# Schema_6.net
KiCad netlist of a schematic drawn in EAGLE
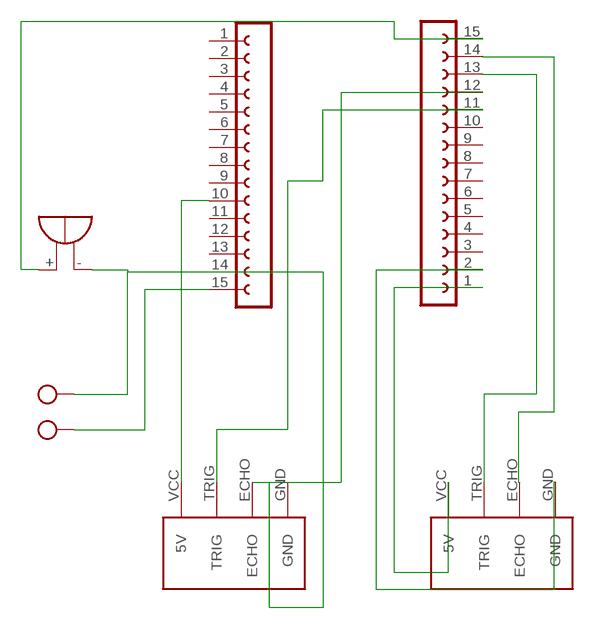
[diagram p0: schematic, sheet 1]

(export (version "E")
  (design (tool "Eeschema 10.0.6"))
  (components
    (comp (ref "J_ULTRASONIC_3")
      (value "HC-SR04")
      (footprint "eagle-import:HC-SR04_FOOTPRINT")
      (libsource (lib "eagle-import") (part "HC-SR04"))
    )
    (comp (ref "J_ULTRASONIC_4")
      (value "HC-SR04")
      (footprint "eagle-import:HC-SR04_FOOTPRINT")
      (libsource (lib "eagle-import") (part "HC-SR04"))
    )
    (comp (ref "SG2")
      (value "EB2505")
      (footprint "eagle-import:EB2505")
      (libsource (lib "eagle-import") (part "EB2505"))
    )
    (comp (ref "SV1")
      (value "FE15-1")
      (footprint "eagle-import:FE15")
      (libsource (lib "eagle-import") (part "FE15-1"))
    )
    (comp (ref "SV2")
      (value "FE15-1")
      (footprint "eagle-import:FE15")
      (libsource (lib "eagle-import") (part "FE15-1"))
    )
    (comp (ref "X1")
      (value "AK500/2-H")
      (footprint "eagle-import:AK500_2-H")
      (libsource (lib "eagle-import") (part "AK500/2-H"))
    )
  )
  (nets
    (net (code "1") (name "Net-(J_ULTRASONIC_3-5V)") (class "Default")
      (node (ref "J_ULTRASONIC_3") (pin "VCC") (pinfunction "5V_VCC") (pintype "bidirectional"))
      (node (ref "SV1") (pin "1") (pinfunction "1_1") (pintype "passive"))
    )
    (net (code "2") (name "Net-(J_ULTRASONIC_3-PadECHO)") (class "Default")
      (node (ref "J_ULTRASONIC_3") (pin "ECHO") (pinfunction "ECHO_ECHO") (pintype "bidirectional"))
      (node (ref "SV1") (pin "14") (pinfunction "14_14") (pintype "passive"))
    )
    (net (code "3") (name "Net-(J_ULTRASONIC_3-PadGND)") (class "Default")
      (node (ref "J_ULTRASONIC_3") (pin "GND") (pinfunction "GND_GND") (pintype "bidirectional"))
      (node (ref "SV1") (pin "2") (pinfunction "2_2") (pintype "passive"))
    )
    (net (code "4") (name "Net-(J_ULTRASONIC_3-PadTRIG)") (class "Default")
      (node (ref "J_ULTRASONIC_3") (pin "TRIG") (pinfunction "TRIG_TRIG") (pintype "bidirectional"))
      (node (ref "SV1") (pin "13") (pinfunction "13_13") (pintype "passive"))
    )
    (net (code "5") (name "Net-(J_ULTRASONIC_4-5V)") (class "Default")
      (node (ref "J_ULTRASONIC_4") (pin "VCC") (pinfunction "5V_VCC") (pintype "bidirectional"))
      (node (ref "SV2") (pin "10") (pinfunction "10_10") (pintype "passive"))
    )
    (net (code "6") (name "Net-(J_ULTRASONIC_4-PadECHO)") (class "Default")
      (node (ref "J_ULTRASONIC_4") (pin "ECHO") (pinfunction "ECHO_ECHO") (pintype "bidirectional"))
      (node (ref "SV1") (pin "12") (pinfunction "12_12") (pintype "passive"))
    )
    (net (code "7") (name "Net-(J_ULTRASONIC_4-PadTRIG)") (class "Default")
      (node (ref "J_ULTRASONIC_4") (pin "TRIG") (pinfunction "TRIG_TRIG") (pintype "bidirectional"))
      (node (ref "SV1") (pin "11") (pinfunction "11_11") (pintype "passive"))
    )
    (net (code "8") (name "Net-(SG2-Pad+)") (class "Default")
      (node (ref "SG2") (pin "+") (pinfunction "+_+") (pintype "passive"))
      (node (ref "SV1") (pin "15") (pinfunction "15_15") (pintype "passive"))
    )
    (net (code "9") (name "Net-(X1A-KL)") (class "Default")
      (node (ref "J_ULTRASONIC_4") (pin "GND") (pinfunction "GND_GND") (pintype "bidirectional"))
      (node (ref "SG2") (pin "-") (pinfunction "-_-") (pintype "passive"))
      (node (ref "SV2") (pin "14") (pinfunction "14_14") (pintype "passive"))
      (node (ref "X1") (pin "1") (pinfunction "KL_1") (pintype "passive"))
    )
    (net (code "10") (name "Net-(X1B-KL)") (class "Default")
      (node (ref "SV2") (pin "15") (pinfunction "15_15") (pintype "passive"))
      (node (ref "X1") (pin "2") (pinfunction "KL_2") (pintype "passive"))
    )
    (net (code "11") (name "unconnected-(SV1-Pad3)") (class "Default")
      (node (ref "SV1") (pin "3") (pinfunction "3_3") (pintype "passive"))
    )
    (net (code "12") (name "unconnected-(SV1-Pad4)") (class "Default")
      (node (ref "SV1") (pin "4") (pinfunction "4_4") (pintype "passive"))
    )
    (net (code "13") (name "unconnected-(SV1-Pad5)") (class "Default")
      (node (ref "SV1") (pin "5") (pinfunction "5_5") (pintype "passive"))
    )
    (net (code "14") (name "unconnected-(SV1-Pad6)") (class "Default")
      (node (ref "SV1") (pin "6") (pinfunction "6_6") (pintype "passive"))
    )
    (net (code "15") (name "unconnected-(SV1-Pad7)") (class "Default")
      (node (ref "SV1") (pin "7") (pinfunction "7_7") (pintype "passive"))
    )
    (net (code "16") (name "unconnected-(SV1-Pad8)") (class "Default")
      (node (ref "SV1") (pin "8") (pinfunction "8_8") (pintype "passive"))
    )
    (net (code "17") (name "unconnected-(SV1-Pad9)") (class "Default")
      (node (ref "SV1") (pin "9") (pinfunction "9_9") (pintype "passive"))
    )
    (net (code "18") (name "unconnected-(SV1-Pad10)") (class "Default")
      (node (ref "SV1") (pin "10") (pinfunction "10_10") (pintype "passive"))
    )
    (net (code "19") (name "unconnected-(SV2-Pad1)") (class "Default")
      (node (ref "SV2") (pin "1") (pinfunction "1_1") (pintype "passive"))
    )
    (net (code "20") (name "unconnected-(SV2-Pad2)") (class "Default")
      (node (ref "SV2") (pin "2") (pinfunction "2_2") (pintype "passive"))
    )
    (net (code "21") (name "unconnected-(SV2-Pad3)") (class "Default")
      (node (ref "SV2") (pin "3") (pinfunction "3_3") (pintype "passive"))
    )
    (net (code "22") (name "unconnected-(SV2-Pad4)") (class "Default")
      (node (ref "SV2") (pin "4") (pinfunction "4_4") (pintype "passive"))
    )
    (net (code "23") (name "unconnected-(SV2-Pad5)") (class "Default")
      (node (ref "SV2") (pin "5") (pinfunction "5_5") (pintype "passive"))
    )
    (net (code "24") (name "unconnected-(SV2-Pad6)") (class "Default")
      (node (ref "SV2") (pin "6") (pinfunction "6_6") (pintype "passive"))
    )
    (net (code "25") (name "unconnected-(SV2-Pad7)") (class "Default")
      (node (ref "SV2") (pin "7") (pinfunction "7_7") (pintype "passive"))
    )
    (net (code "26") (name "unconnected-(SV2-Pad8)") (class "Default")
      (node (ref "SV2") (pin "8") (pinfunction "8_8") (pintype "passive"))
    )
    (net (code "27") (name "unconnected-(SV2-Pad9)") (class "Default")
      (node (ref "SV2") (pin "9") (pinfunction "9_9") (pintype "passive"))
    )
    (net (code "28") (name "unconnected-(SV2-Pad11)") (class "Default")
      (node (ref "SV2") (pin "11") (pinfunction "11_11") (pintype "passive"))
    )
    (net (code "29") (name "unconnected-(SV2-Pad12)") (class "Default")
      (node (ref "SV2") (pin "12") (pinfunction "12_12") (pintype "passive"))
    )
    (net (code "30") (name "unconnected-(SV2-Pad13)") (class "Default")
      (node (ref "SV2") (pin "13") (pinfunction "13_13") (pintype "passive"))
    )
  )
)
